# Connectors.net
KiCad netlist of a schematic drawn in Altium Designer
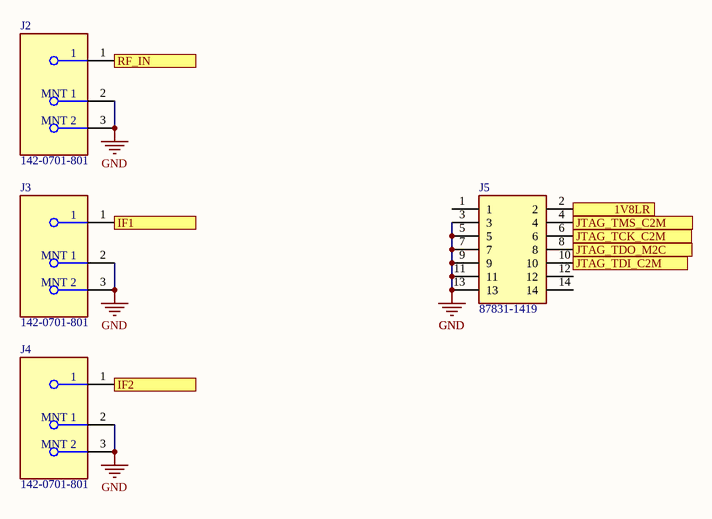
[diagram p0: Connectors.SchDoc]

(export (version "E")
  (design (tool "Eeschema 10.0.6"))
  (components
    (comp (ref "J2")
      (value "142-0701-801")
      (footprint "FP-142-0701-801-MFG")
      (description "CONN SMA JACK STR 50OHM EDGE MNT")
      (libsource (lib "Altium Content Vault") (part "89929399afe843c8b6880c6cbd0f99a"))
    )
    (comp (ref "J3")
      (value "142-0701-801")
      (footprint "FP-142-0701-801-MFG")
      (description "CONN SMA JACK STR 50OHM EDGE MNT")
      (libsource (lib "Altium Content Vault") (part "89929399afe843c8b6880c6cbd0f99a"))
    )
    (comp (ref "J4")
      (value "142-0701-801")
      (footprint "FP-142-0701-801-MFG")
      (description "CONN SMA JACK STR 50OHM EDGE MNT")
      (libsource (lib "Altium Content Vault") (part "89929399afe843c8b6880c6cbd0f99a"))
    )
    (comp (ref "J5")
      (value "87831-1419")
      (footprint "SamacSys:SHDR14W55P200_2X7_1665X630X640P")
      (description "Connector")
      (fields (field (name "MOUSER PART NUMBER") "538-87831-1419"))
      (libsource (lib "*") (part "87831-1419"))
    )
  )
  (nets
    (net (code "1") (name "/1V8LR") (class "Default")
      (node (ref "J5") (pin "2") (pinfunction "2_2") (pintype "passive"))
    )
    (net (code "2") (name "/IF1") (class "Default")
      (node (ref "J3") (pin "1") (pinfunction "1_1") (pintype "passive"))
    )
    (net (code "3") (name "/IF2") (class "Default")
      (node (ref "J4") (pin "1") (pinfunction "1_1") (pintype "passive"))
    )
    (net (code "4") (name "/JTAG_TCK_C2M") (class "Default")
      (node (ref "J5") (pin "6") (pinfunction "6_6") (pintype "passive"))
    )
    (net (code "5") (name "/JTAG_TDI_C2M") (class "Default")
      (node (ref "J5") (pin "10") (pinfunction "10_10") (pintype "passive"))
    )
    (net (code "6") (name "/JTAG_TDO_M2C") (class "Default")
      (node (ref "J5") (pin "8") (pinfunction "8_8") (pintype "passive"))
    )
    (net (code "7") (name "/JTAG_TMS_C2M") (class "Default")
      (node (ref "J5") (pin "4") (pinfunction "4_4") (pintype "passive"))
    )
    (net (code "8") (name "/RF_IN") (class "Default")
      (node (ref "J2") (pin "1") (pinfunction "1_1") (pintype "passive"))
    )
    (net (code "9") (name "GND") (class "Default")
      (node (ref "J2") (pin "2") (pinfunction "MNT_1_2") (pintype "passive"))
      (node (ref "J2") (pin "3") (pinfunction "MNT_2_3") (pintype "passive"))
      (node (ref "J3") (pin "2") (pinfunction "MNT_1_2") (pintype "passive"))
      (node (ref "J3") (pin "3") (pinfunction "MNT_2_3") (pintype "passive"))
      (node (ref "J4") (pin "2") (pinfunction "MNT_1_2") (pintype "passive"))
      (node (ref "J4") (pin "3") (pinfunction "MNT_2_3") (pintype "passive"))
      (node (ref "J5") (pin "11") (pinfunction "11_11") (pintype "passive"))
      (node (ref "J5") (pin "13") (pinfunction "13_13") (pintype "passive"))
      (node (ref "J5") (pin "3") (pinfunction "3_3") (pintype "passive"))
      (node (ref "J5") (pin "5") (pinfunction "5_5") (pintype "passive"))
      (node (ref "J5") (pin "7") (pinfunction "7_7") (pintype "passive"))
      (node (ref "J5") (pin "9") (pinfunction "9_9") (pintype "passive"))
    )
    (net (code "10") (name "unconnected-(J5-Pad1)") (class "Default")
      (node (ref "J5") (pin "1") (pinfunction "1_1") (pintype "passive"))
    )
    (net (code "11") (name "unconnected-(J5-Pad12)") (class "Default")
      (node (ref "J5") (pin "12") (pinfunction "12_12") (pintype "passive"))
    )
    (net (code "12") (name "unconnected-(J5-Pad14)") (class "Default")
      (node (ref "J5") (pin "14") (pinfunction "14_14") (pintype "passive"))
    )
  )
)
